# ElevenR3.net
KiCad netlist of a schematic drawn in EAGLE
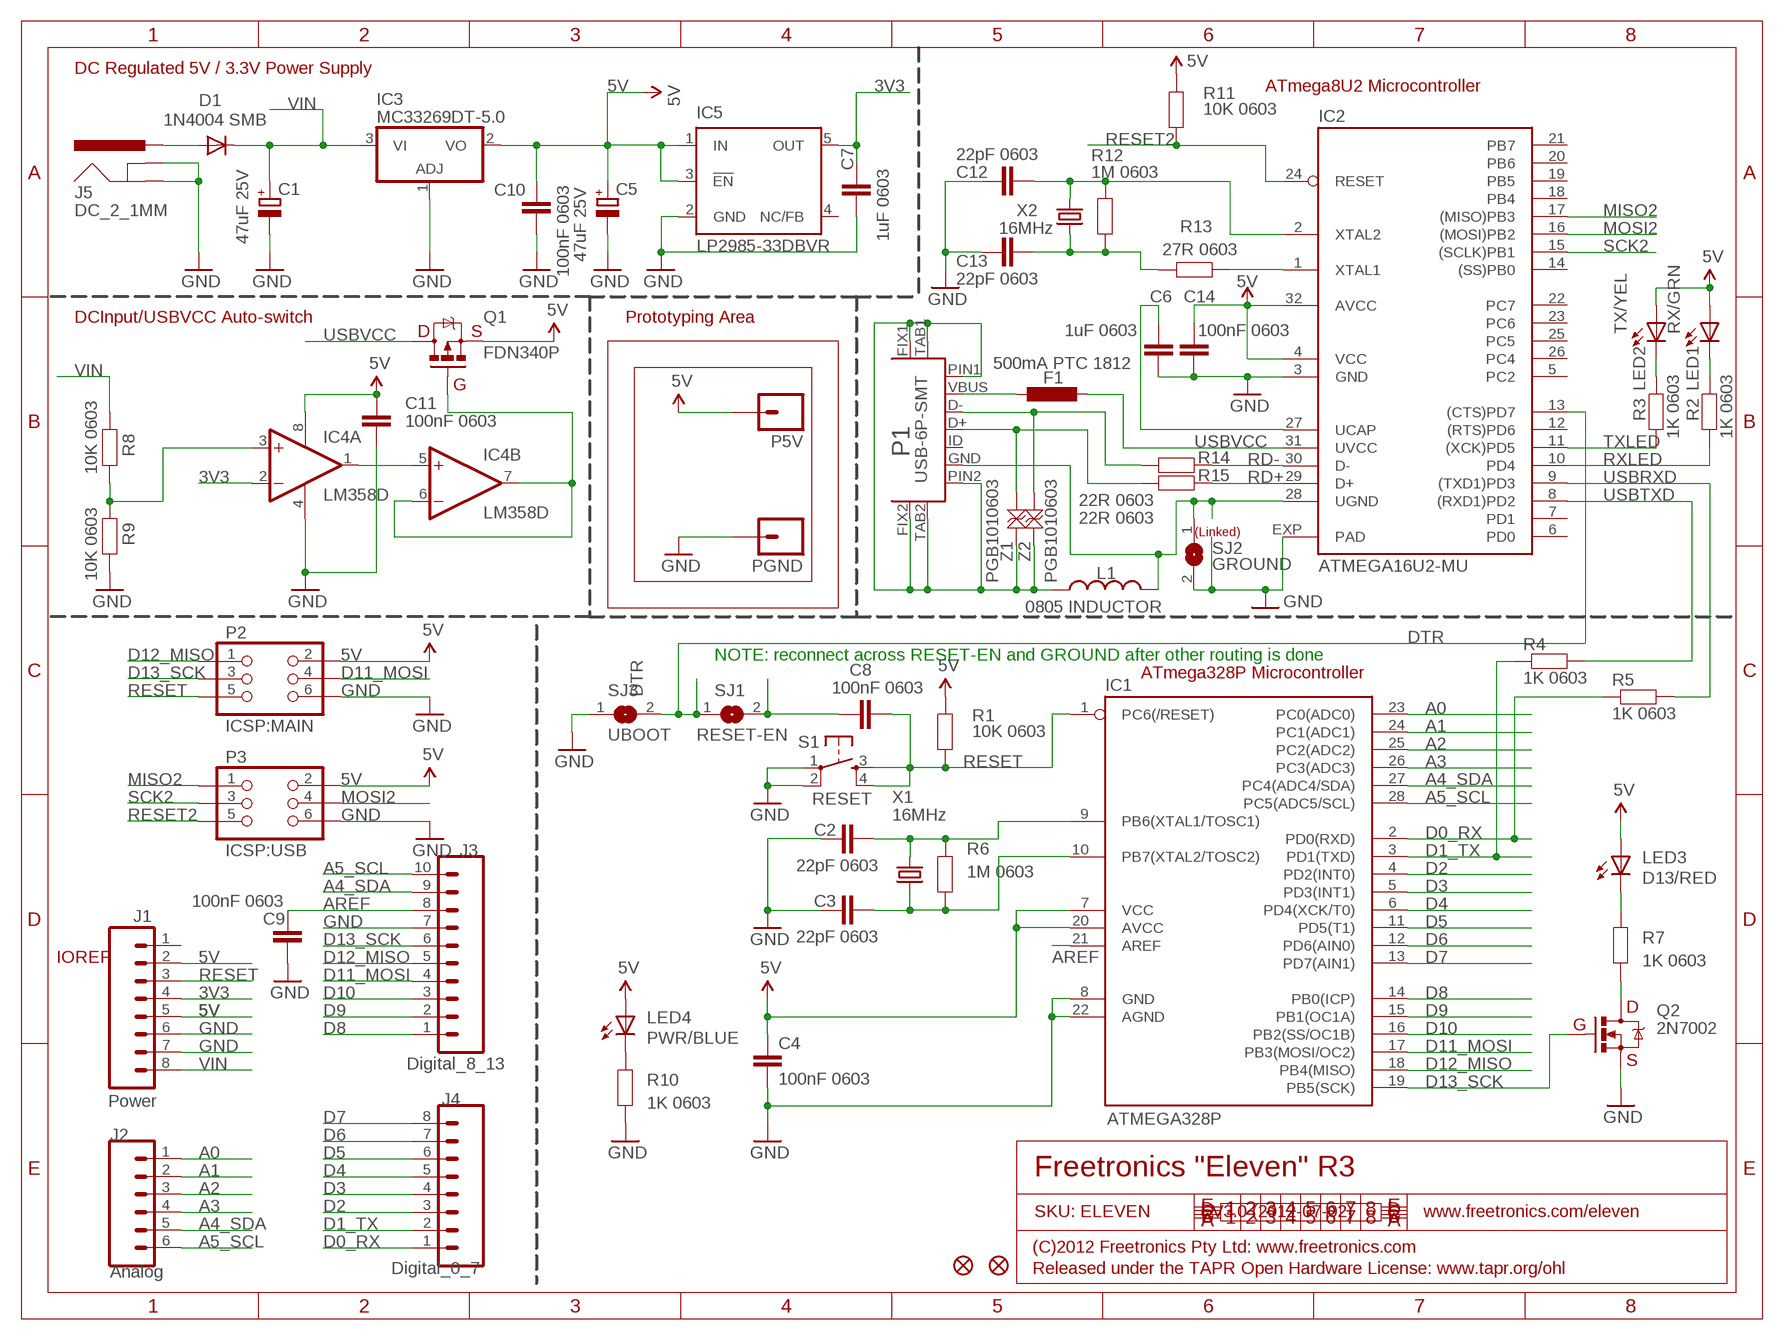
[diagram p0: schematic, sheet 1]

(export (version "E")
  (design (tool "Eeschema 10.0.6"))
  (components
    (comp (ref "C1")
      (value "47uF 25V")
      (footprint "eagle-import:PANASONIC_D")
      (libsource (lib "eagle-import") (part "CPOL-EUD"))
    )
    (comp (ref "C2")
      (value "22pF 0603")
      (footprint "eagle-import:C0603")
      (libsource (lib "eagle-import") (part "CAP0603"))
    )
    (comp (ref "C3")
      (value "22pF 0603")
      (footprint "eagle-import:C0603")
      (libsource (lib "eagle-import") (part "CAP0603"))
    )
    (comp (ref "C4")
      (value "100nF 0603")
      (footprint "eagle-import:C0603")
      (libsource (lib "eagle-import") (part "CAP0603"))
    )
    (comp (ref "C5")
      (value "47uF 25V")
      (footprint "eagle-import:PANASONIC_D")
      (libsource (lib "eagle-import") (part "CPOL-EUD"))
    )
    (comp (ref "C6")
      (value "1uF 0603")
      (footprint "eagle-import:C0603")
      (libsource (lib "eagle-import") (part "CAP0603"))
    )
    (comp (ref "C7")
      (value "1uF 0603")
      (footprint "eagle-import:C0603")
      (libsource (lib "eagle-import") (part "CAP0603"))
    )
    (comp (ref "C8")
      (value "100nF 0603")
      (footprint "eagle-import:C0603")
      (libsource (lib "eagle-import") (part "CAP0603"))
    )
    (comp (ref "C9")
      (value "100nF 0603")
      (footprint "eagle-import:C0603")
      (libsource (lib "eagle-import") (part "CAP0603"))
    )
    (comp (ref "C10")
      (value "100nF 0603")
      (footprint "eagle-import:C0603")
      (libsource (lib "eagle-import") (part "CAP0603"))
    )
    (comp (ref "C11")
      (value "100nF 0603")
      (footprint "eagle-import:C0603")
      (libsource (lib "eagle-import") (part "CAP0603"))
    )
    (comp (ref "C12")
      (value "22pF 0603")
      (footprint "eagle-import:C0603")
      (libsource (lib "eagle-import") (part "CAP0603"))
    )
    (comp (ref "C13")
      (value "22pF 0603")
      (footprint "eagle-import:C0603")
      (libsource (lib "eagle-import") (part "CAP0603"))
    )
    (comp (ref "C14")
      (value "100nF 0603")
      (footprint "eagle-import:C0603")
      (libsource (lib "eagle-import") (part "CAP0603"))
    )
    (comp (ref "D1")
      (value "1N4004 SMB")
      (footprint "eagle-import:SMA-DIODE")
      (libsource (lib "eagle-import") (part "DIODESMA"))
    )
    (comp (ref "F1")
      (value "500mA PTC 1812")
      (footprint "eagle-import:L1812")
      (libsource (lib "eagle-import") (part "L-EUL1812"))
    )
    (comp (ref "IC1")
      (value "ATMEGA328P")
      (footprint "eagle-import:DIL28-3")
      (libsource (lib "eagle-import") (part "AVR-MEGA8-P"))
    )
    (comp (ref "IC2")
      (value "ATMEGA16U2-MU")
      (footprint "eagle-import:ATMEL_QFN32")
      (libsource (lib "eagle-import") (part "ATMEGA8U2QFN"))
    )
    (comp (ref "IC3")
      (value "MC33269DT-5.0")
      (footprint "eagle-import:DPACK")
      (libsource (lib "eagle-import") (part "MC33269-X-D-5.0"))
    )
    (comp (ref "IC4")
      (value "LM358D")
      (footprint "eagle-import:SO08")
      (libsource (lib "eagle-import") (part "LM358D"))
    )
    (comp (ref "IC5")
      (value "LP2985-33DBVR")
      (footprint "eagle-import:TEXAS_SOT23-DBV")
      (libsource (lib "eagle-import") (part "LP2985-XX33"))
    )
    (comp (ref "J1")
      (value "Power")
      (footprint "eagle-import:1X08-S")
      (libsource (lib "eagle-import") (part "M08-SOCKET"))
    )
    (comp (ref "J2")
      (value "Analog")
      (footprint "eagle-import:1X06-S")
      (libsource (lib "eagle-import") (part "M06-SOCKET"))
    )
    (comp (ref "J3")
      (value "Digital_8_13")
      (footprint "eagle-import:1X10-S")
      (libsource (lib "eagle-import") (part "M10-SOCKET"))
    )
    (comp (ref "J4")
      (value "Digital_0_7")
      (footprint "eagle-import:1X08-S")
      (libsource (lib "eagle-import") (part "M08-SOCKET"))
    )
    (comp (ref "J5")
      (value "DC_2_1MM")
      (footprint "eagle-import:POWER_JACK_SLOTS")
      (libsource (lib "eagle-import") (part "POWER_JACK-SLOTS"))
    )
    (comp (ref "L1")
      (value "0805 INDUCTOR")
      (footprint "eagle-import:0805-LARGE")
      (libsource (lib "eagle-import") (part "INDUCTOR0805-LARGE"))
    )
    (comp (ref "LED1")
      (value "RX/GRN")
      (footprint "eagle-import:LED-0603")
      (libsource (lib "eagle-import") (part "LED0603"))
    )
    (comp (ref "LED2")
      (value "TX/YEL")
      (footprint "eagle-import:LED-0603")
      (libsource (lib "eagle-import") (part "LED0603"))
    )
    (comp (ref "LED3")
      (value "D13/RED")
      (footprint "eagle-import:LED-0603")
      (libsource (lib "eagle-import") (part "LED0603"))
    )
    (comp (ref "LED4")
      (value "PWR/BLUE")
      (footprint "eagle-import:LED-0603")
      (libsource (lib "eagle-import") (part "LED0603"))
    )
    (comp (ref "P1")
      (value "USB-6P-SMT")
      (footprint "eagle-import:USB-MICROB-MB05PMXX")
      (libsource (lib "eagle-import") (part "USB-6P-SMT"))
    )
    (comp (ref "P2")
      (value "ICSP:MAIN")
      (footprint "eagle-import:2X03PTH")
      (libsource (lib "eagle-import") (part "ICSPPTH"))
    )
    (comp (ref "P3")
      (value "ICSP:USB")
      (footprint "eagle-import:2X03PTH")
      (libsource (lib "eagle-import") (part "ICSPPTH"))
    )
    (comp (ref "P5V")
      (value "M01SMD")
      (footprint "eagle-import:LUXEON-PAD")
      (libsource (lib "eagle-import") (part "M01SMD"))
    )
    (comp (ref "PGND")
      (value "M01SMD")
      (footprint "eagle-import:LUXEON-PAD")
      (libsource (lib "eagle-import") (part "M01SMD"))
    )
    (comp (ref "Q1")
      (value "FDN340P")
      (footprint "eagle-import:SOT23-3")
      (libsource (lib "eagle-import") (part "MOSFET-PCHANNEL-SMT"))
    )
    (comp (ref "Q2")
      (value "2N7002")
      (footprint "eagle-import:SOT23-3")
      (libsource (lib "eagle-import") (part "MOSFET-NCHANNELSMD"))
    )
    (comp (ref "R1")
      (value "10K 0603")
      (footprint "eagle-import:R0603")
      (libsource (lib "eagle-import") (part "RESISTOR0603"))
    )
    (comp (ref "R2")
      (value "1K 0603")
      (footprint "eagle-import:R0603")
      (libsource (lib "eagle-import") (part "RESISTOR0603"))
    )
    (comp (ref "R3")
      (value "1K 0603")
      (footprint "eagle-import:R0603")
      (libsource (lib "eagle-import") (part "RESISTOR0603"))
    )
    (comp (ref "R4")
      (value "1K 0603")
      (footprint "eagle-import:R0603")
      (libsource (lib "eagle-import") (part "RESISTOR0603"))
    )
    (comp (ref "R5")
      (value "1K 0603")
      (footprint "eagle-import:R0603")
      (libsource (lib "eagle-import") (part "RESISTOR0603"))
    )
    (comp (ref "R6")
      (value "1M 0603")
      (footprint "eagle-import:R0603")
      (libsource (lib "eagle-import") (part "RESISTOR0603"))
    )
    (comp (ref "R7")
      (value "1K 0603")
      (footprint "eagle-import:R0603")
      (libsource (lib "eagle-import") (part "RESISTOR0603"))
    )
    (comp (ref "R8")
      (value "10K 0603")
      (footprint "eagle-import:R0603")
      (libsource (lib "eagle-import") (part "RESISTOR0603"))
    )
    (comp (ref "R9")
      (value "10K 0603")
      (footprint "eagle-import:R0603")
      (libsource (lib "eagle-import") (part "RESISTOR0603"))
    )
    (comp (ref "R10")
      (value "1K 0603")
      (footprint "eagle-import:R0603")
      (libsource (lib "eagle-import") (part "RESISTOR0603"))
    )
    (comp (ref "R11")
      (value "10K 0603")
      (footprint "eagle-import:R0603")
      (libsource (lib "eagle-import") (part "RESISTOR0603"))
    )
    (comp (ref "R12")
      (value "1M 0603")
      (footprint "eagle-import:R0603")
      (libsource (lib "eagle-import") (part "RESISTOR0603"))
    )
    (comp (ref "R13")
      (value "27R 0603")
      (footprint "eagle-import:R0603")
      (libsource (lib "eagle-import") (part "RESISTOR0603"))
    )
    (comp (ref "R14")
      (value "22R 0603")
      (footprint "eagle-import:R0603")
      (libsource (lib "eagle-import") (part "RESISTOR0603"))
    )
    (comp (ref "R15")
      (value "22R 0603")
      (footprint "eagle-import:R0603")
      (libsource (lib "eagle-import") (part "RESISTOR0603"))
    )
    (comp (ref "S1")
      (value "RESET")
      (footprint "eagle-import:TACTILE_SMD-6MM")
      (libsource (lib "eagle-import") (part "TAC_SWITCH-SMT-6"))
    )
    (comp (ref "SJ1")
      (value "RESET-EN")
      (footprint "eagle-import:SJ")
      (libsource (lib "eagle-import") (part "SJ"))
    )
    (comp (ref "SJ2")
      (value "GROUND")
      (footprint "eagle-import:SJ")
      (libsource (lib "eagle-import") (part "SJ"))
    )
    (comp (ref "SJ3")
      (value "UBOOT")
      (footprint "eagle-import:SJ")
      (libsource (lib "eagle-import") (part "SJ"))
    )
    (comp (ref "U$5")
      (value "FIDUCIAL1X2.5")
      (footprint "eagle-import:FIDUCIAL-1X2.5")
      (libsource (lib "eagle-import") (part "FIDUCIAL1X2.5"))
    )
    (comp (ref "U$14")
      (value "FIDUCIAL1X2.5")
      (footprint "eagle-import:FIDUCIAL-1X2.5")
      (libsource (lib "eagle-import") (part "FIDUCIAL1X2.5"))
    )
    (comp (ref "X1")
      (value "16MHz")
      (footprint "eagle-import:HC49U-V")
      (libsource (lib "eagle-import") (part "CRYSTALHC49UV"))
    )
    (comp (ref "X2")
      (value "16MHz")
      (footprint "eagle-import:HC49U-V")
      (libsource (lib "eagle-import") (part "CRYSTALHC49UV"))
    )
    (comp (ref "Z1")
      (value "PGB1010603")
      (footprint "eagle-import:TVS0603")
      (libsource (lib "eagle-import") (part "TVS0603"))
    )
    (comp (ref "Z2")
      (value "PGB1010603")
      (footprint "eagle-import:TVS0603")
      (libsource (lib "eagle-import") (part "TVS0603"))
    )
  )
  (nets
    (net (code "1") (name "/3V3") (class "Default")
      (node (ref "C7") (pin "2") (pinfunction "2_2") (pintype "passive"))
      (node (ref "IC4") (pin "2") (pinfunction "-IN_2") (pintype "input"))
      (node (ref "IC5") (pin "5") (pinfunction "OUT_5") (pintype "passive"))
      (node (ref "J1") (pin "4") (pinfunction "4_4") (pintype "passive"))
    )
    (net (code "2") (name "/A0") (class "Default")
      (node (ref "IC1") (pin "23") (pinfunction "PC0(ADC0)_23") (pintype "bidirectional"))
      (node (ref "J2") (pin "1") (pinfunction "1_1") (pintype "passive"))
    )
    (net (code "3") (name "/A1") (class "Default")
      (node (ref "IC1") (pin "24") (pinfunction "PC1(ADC1)_24") (pintype "bidirectional"))
      (node (ref "J2") (pin "2") (pinfunction "2_2") (pintype "passive"))
    )
    (net (code "4") (name "/A2") (class "Default")
      (node (ref "IC1") (pin "25") (pinfunction "PC2(ADC2)_25") (pintype "bidirectional"))
      (node (ref "J2") (pin "3") (pinfunction "3_3") (pintype "passive"))
    )
    (net (code "5") (name "/A3") (class "Default")
      (node (ref "IC1") (pin "26") (pinfunction "PC3(ADC3)_26") (pintype "bidirectional"))
      (node (ref "J2") (pin "4") (pinfunction "4_4") (pintype "passive"))
    )
    (net (code "6") (name "/A4_SDA") (class "Default")
      (node (ref "IC1") (pin "27") (pinfunction "PC4(ADC4/SDA)_27") (pintype "bidirectional"))
      (node (ref "J2") (pin "5") (pinfunction "5_5") (pintype "passive"))
      (node (ref "J3") (pin "9") (pinfunction "9_9") (pintype "passive"))
    )
    (net (code "7") (name "/A5_SCL") (class "Default")
      (node (ref "IC1") (pin "28") (pinfunction "PC5(ADC5/SCL)_28") (pintype "bidirectional"))
      (node (ref "J2") (pin "6") (pinfunction "6_6") (pintype "passive"))
      (node (ref "J3") (pin "10") (pinfunction "10_10") (pintype "passive"))
    )
    (net (code "8") (name "/AREF") (class "Default")
      (node (ref "C9") (pin "1") (pinfunction "1_1") (pintype "passive"))
      (node (ref "IC1") (pin "21") (pinfunction "AREF_21") (pintype "bidirectional"))
      (node (ref "J3") (pin "8") (pinfunction "8_8") (pintype "passive"))
    )
    (net (code "9") (name "/D0_RX") (class "Default")
      (node (ref "IC1") (pin "2") (pinfunction "PD0(RXD)_2") (pintype "bidirectional"))
      (node (ref "J4") (pin "1") (pinfunction "1_1") (pintype "passive"))
      (node (ref "R5") (pin "1") (pinfunction "1_1") (pintype "passive"))
    )
    (net (code "10") (name "/D1_TX") (class "Default")
      (node (ref "IC1") (pin "3") (pinfunction "PD1(TXD)_3") (pintype "bidirectional"))
      (node (ref "J4") (pin "2") (pinfunction "2_2") (pintype "passive"))
      (node (ref "R4") (pin "1") (pinfunction "1_1") (pintype "passive"))
    )
    (net (code "11") (name "/D2") (class "Default")
      (node (ref "IC1") (pin "4") (pinfunction "PD2(INT0)_4") (pintype "bidirectional"))
      (node (ref "J4") (pin "3") (pinfunction "3_3") (pintype "passive"))
    )
    (net (code "12") (name "/D3") (class "Default")
      (node (ref "IC1") (pin "5") (pinfunction "PD3(INT1)_5") (pintype "bidirectional"))
      (node (ref "J4") (pin "4") (pinfunction "4_4") (pintype "passive"))
    )
    (net (code "13") (name "/D4") (class "Default")
      (node (ref "IC1") (pin "6") (pinfunction "PD4(XCK/T0)_6") (pintype "bidirectional"))
      (node (ref "J4") (pin "5") (pinfunction "5_5") (pintype "passive"))
    )
    (net (code "14") (name "/D5") (class "Default")
      (node (ref "IC1") (pin "11") (pinfunction "PD5(T1)_11") (pintype "bidirectional"))
      (node (ref "J4") (pin "6") (pinfunction "6_6") (pintype "passive"))
    )
    (net (code "15") (name "/D6") (class "Default")
      (node (ref "IC1") (pin "12") (pinfunction "PD6(AIN0)_12") (pintype "bidirectional"))
      (node (ref "J4") (pin "7") (pinfunction "7_7") (pintype "passive"))
    )
    (net (code "16") (name "/D7") (class "Default")
      (node (ref "IC1") (pin "13") (pinfunction "PD7(AIN1)_13") (pintype "bidirectional"))
      (node (ref "J4") (pin "8") (pinfunction "8_8") (pintype "passive"))
    )
    (net (code "17") (name "/D8") (class "Default")
      (node (ref "IC1") (pin "14") (pinfunction "PB0(ICP)_14") (pintype "bidirectional"))
      (node (ref "J3") (pin "1") (pinfunction "1_1") (pintype "passive"))
    )
    (net (code "18") (name "/D9") (class "Default")
      (node (ref "IC1") (pin "15") (pinfunction "PB1(OC1A)_15") (pintype "bidirectional"))
      (node (ref "J3") (pin "2") (pinfunction "2_2") (pintype "passive"))
    )
    (net (code "19") (name "/D10") (class "Default")
      (node (ref "IC1") (pin "16") (pinfunction "PB2(SS/OC1B)_16") (pintype "bidirectional"))
      (node (ref "J3") (pin "3") (pinfunction "3_3") (pintype "passive"))
    )
    (net (code "20") (name "/D11_MOSI") (class "Default")
      (node (ref "IC1") (pin "17") (pinfunction "PB3(MOSI/OC2)_17") (pintype "bidirectional"))
      (node (ref "J3") (pin "4") (pinfunction "4_4") (pintype "passive"))
      (node (ref "P2") (pin "4") (pinfunction "4_4") (pintype "passive"))
    )
    (net (code "21") (name "/D12_MISO") (class "Default")
      (node (ref "IC1") (pin "18") (pinfunction "PB4(MISO)_18") (pintype "bidirectional"))
      (node (ref "J3") (pin "5") (pinfunction "5_5") (pintype "passive"))
      (node (ref "P2") (pin "1") (pinfunction "1_1") (pintype "passive"))
    )
    (net (code "22") (name "/D13_SCK") (class "Default")
      (node (ref "IC1") (pin "19") (pinfunction "PB5(SCK)_19") (pintype "bidirectional"))
      (node (ref "J3") (pin "6") (pinfunction "6_6") (pintype "passive"))
      (node (ref "P2") (pin "3") (pinfunction "3_3") (pintype "passive"))
      (node (ref "Q2") (pin "1") (pinfunction "G_1") (pintype "passive"))
    )
    (net (code "23") (name "/DTR") (class "Default")
      (node (ref "IC2") (pin "13") (pinfunction "(CTS)PD7_13") (pintype "bidirectional"))
      (node (ref "SJ1") (pin "1") (pinfunction "1_1") (pintype "passive"))
      (node (ref "SJ3") (pin "2") (pinfunction "2_2") (pintype "passive"))
    )
    (net (code "24") (name "/MISO2") (class "Default")
      (node (ref "IC2") (pin "17") (pinfunction "(MISO)PB3_17") (pintype "bidirectional"))
      (node (ref "P3") (pin "1") (pinfunction "1_1") (pintype "passive"))
    )
    (net (code "25") (name "/MOSI2") (class "Default")
      (node (ref "IC2") (pin "16") (pinfunction "(MOSI)PB2_16") (pintype "bidirectional"))
      (node (ref "P3") (pin "4") (pinfunction "4_4") (pintype "passive"))
    )
    (net (code "26") (name "/RD+") (class "Default")
      (node (ref "IC2") (pin "29") (pinfunction "D+_29") (pintype "bidirectional"))
      (node (ref "R15") (pin "1") (pinfunction "1_1") (pintype "passive"))
    )
    (net (code "27") (name "/RD-") (class "Default")
      (node (ref "IC2") (pin "30") (pinfunction "D-_30") (pintype "bidirectional"))
      (node (ref "R14") (pin "1") (pinfunction "1_1") (pintype "passive"))
    )
    (net (code "28") (name "/RESET") (class "Default")
      (node (ref "C8") (pin "2") (pinfunction "2_2") (pintype "passive"))
      (node (ref "IC1") (pin "1") (pinfunction "PC6(/RESET)_1") (pintype "bidirectional"))
      (node (ref "J1") (pin "3") (pinfunction "3_3") (pintype "passive"))
      (node (ref "P2") (pin "5") (pinfunction "5_5") (pintype "passive"))
      (node (ref "R1") (pin "1") (pinfunction "1_1") (pintype "passive"))
      (node (ref "S1") (pin "3") (pinfunction "3_3") (pintype "passive"))
      (node (ref "S1") (pin "4") (pinfunction "4_4") (pintype "passive"))
    )
    (net (code "29") (name "/RESET2") (class "Default")
      (node (ref "IC2") (pin "24") (pinfunction "RESET_24") (pintype "input"))
      (node (ref "P3") (pin "5") (pinfunction "5_5") (pintype "passive"))
      (node (ref "R11") (pin "1") (pinfunction "1_1") (pintype "passive"))
    )
    (net (code "30") (name "/RXLED") (class "Default")
      (node (ref "IC2") (pin "10") (pinfunction "PD4_10") (pintype "bidirectional"))
      (node (ref "R2") (pin "1") (pinfunction "1_1") (pintype "passive"))
    )
    (net (code "31") (name "/SCK2") (class "Default")
      (node (ref "IC2") (pin "15") (pinfunction "(SCLK)PB1_15") (pintype "bidirectional"))
      (node (ref "P3") (pin "3") (pinfunction "3_3") (pintype "passive"))
    )
    (net (code "32") (name "/TXLED") (class "Default")
      (node (ref "IC2") (pin "11") (pinfunction "(XCK)PD5_11") (pintype "bidirectional"))
      (node (ref "R3") (pin "1") (pinfunction "1_1") (pintype "passive"))
    )
    (net (code "33") (name "/USBRXD") (class "Default")
      (node (ref "IC2") (pin "9") (pinfunction "(TXD1)PD3_9") (pintype "bidirectional"))
      (node (ref "R5") (pin "2") (pinfunction "2_2") (pintype "passive"))
    )
    (net (code "34") (name "/USBTXD") (class "Default")
      (node (ref "IC2") (pin "8") (pinfunction "(RXD1)PD2_8") (pintype "bidirectional"))
      (node (ref "R4") (pin "2") (pinfunction "2_2") (pintype "passive"))
    )
    (net (code "35") (name "/USBVCC") (class "Default")
      (node (ref "F1") (pin "2") (pinfunction "2_2") (pintype "passive"))
      (node (ref "IC2") (pin "31") (pinfunction "UVCC_31") (pintype "power_in"))
      (node (ref "Q1") (pin "3") (pinfunction "D_3") (pintype "passive"))
    )
    (net (code "36") (name "/VIN") (class "Default")
      (node (ref "C1") (pin "+") (pinfunction "+_+") (pintype "passive"))
      (node (ref "D1") (pin "C") (pinfunction "C_C") (pintype "passive"))
      (node (ref "IC3") (pin "3") (pinfunction "VI_3") (pintype "input"))
      (node (ref "J1") (pin "8") (pinfunction "8_8") (pintype "passive"))
      (node (ref "R8") (pin "2") (pinfunction "2_2") (pintype "passive"))
    )
    (net (code "37") (name "5V") (class "Default")
      (node (ref "C10") (pin "1") (pinfunction "1_1") (pintype "passive"))
      (node (ref "C11") (pin "1") (pinfunction "1_1") (pintype "passive"))
      (node (ref "C14") (pin "1") (pinfunction "1_1") (pintype "passive"))
      (node (ref "C4") (pin "1") (pinfunction "1_1") (pintype "passive"))
      (node (ref "C5") (pin "+") (pinfunction "+_+") (pintype "passive"))
      (node (ref "IC1") (pin "20") (pinfunction "AVCC_20") (pintype "bidirectional"))
      (node (ref "IC1") (pin "7") (pinfunction "VCC_7") (pintype "bidirectional"))
      (node (ref "IC2") (pin "32") (pinfunction "AVCC_32") (pintype "power_in"))
      (node (ref "IC2") (pin "4") (pinfunction "VCC_4") (pintype "power_in"))
      (node (ref "IC3") (pin "2") (pinfunction "VO_2") (pintype "passive"))
      (node (ref "IC4") (pin "8") (pinfunction "V+_8") (pintype "power_in"))
      (node (ref "IC5") (pin "1") (pinfunction "IN_1") (pintype "input"))
      (node (ref "IC5") (pin "3") (pinfunction "~{EN}_3") (pintype "input"))
      (node (ref "J1") (pin "2") (pinfunction "2_2") (pintype "passive"))
      (node (ref "J1") (pin "5") (pinfunction "5_5") (pintype "passive"))
      (node (ref "LED1") (pin "A") (pinfunction "A_A") (pintype "passive"))
      (node (ref "LED2") (pin "A") (pinfunction "A_A") (pintype "passive"))
      (node (ref "LED3") (pin "A") (pinfunction "A_A") (pintype "passive"))
      (node (ref "LED4") (pin "A") (pinfunction "A_A") (pintype "passive"))
      (node (ref "P2") (pin "2") (pinfunction "2_2") (pintype "passive"))
      (node (ref "P3") (pin "2") (pinfunction "2_2") (pintype "passive"))
      (node (ref "P5V") (pin "P$1") (pinfunction "1_P$1") (pintype "passive"))
      (node (ref "Q1") (pin "2") (pinfunction "S_2") (pintype "passive"))
      (node (ref "R1") (pin "2") (pinfunction "2_2") (pintype "passive"))
      (node (ref "R11") (pin "2") (pinfunction "2_2") (pintype "passive"))
    )
    (net (code "38") (name "GND") (class "Default")
      (node (ref "C1") (pin "-") (pinfunction "-_-") (pintype "passive"))
      (node (ref "C10") (pin "2") (pinfunction "2_2") (pintype "passive"))
      (node (ref "C11") (pin "2") (pinfunction "2_2") (pintype "passive"))
      (node (ref "C12") (pin "1") (pinfunction "1_1") (pintype "passive"))
      (node (ref "C13") (pin "1") (pinfunction "1_1") (pintype "passive"))
      (node (ref "C14") (pin "2") (pinfunction "2_2") (pintype "passive"))
      (node (ref "C2") (pin "1") (pinfunction "1_1") (pintype "passive"))
      (node (ref "C3") (pin "1") (pinfunction "1_1") (pintype "passive"))
      (node (ref "C4") (pin "2") (pinfunction "2_2") (pintype "passive"))
      (node (ref "C5") (pin "-") (pinfunction "-_-") (pintype "passive"))
      (node (ref "C6") (pin "2") (pinfunction "2_2") (pintype "passive"))
      (node (ref "C7") (pin "1") (pinfunction "1_1") (pintype "passive"))
      (node (ref "C9") (pin "2") (pinfunction "2_2") (pintype "passive"))
      (node (ref "IC1") (pin "22") (pinfunction "AGND_22") (pintype "bidirectional"))
      (node (ref "IC1") (pin "8") (pinfunction "GND_8") (pintype "bidirectional"))
      (node (ref "IC2") (pin "3") (pinfunction "GND_3") (pintype "power_in"))
      (node (ref "IC2") (pin "EXP") (pinfunction "PAD_EXP") (pintype "power_in"))
      (node (ref "IC3") (pin "1") (pinfunction "ADJ_1") (pintype "input"))
      (node (ref "IC4") (pin "4") (pinfunction "V-_4") (pintype "power_in"))
      (node (ref "IC5") (pin "2") (pinfunction "GND_2") (pintype "power_in"))
      (node (ref "J1") (pin "6") (pinfunction "6_6") (pintype "passive"))
      (node (ref "J1") (pin "7") (pinfunction "7_7") (pintype "passive"))
      (node (ref "J3") (pin "7") (pinfunction "7_7") (pintype "passive"))
      (node (ref "J5") (pin "GND") (pinfunction "GND_GND") (pintype "bidirectional"))
      (node (ref "J5") (pin "GNDBREAK") (pinfunction "GNDBREAK_GNDBREAK") (pintype "bidirectional"))
      (node (ref "P2") (pin "6") (pinfunction "6_6") (pintype "passive"))
      (node (ref "P3") (pin "6") (pinfunction "6_6") (pintype "passive"))
      (node (ref "PGND") (pin "P$1") (pinfunction "1_P$1") (pintype "passive"))
      (node (ref "Q2") (pin "2") (pinfunction "S_2") (pintype "passive"))
      (node (ref "R10") (pin "1") (pinfunction "1_1") (pintype "passive"))
      (node (ref "R9") (pin "1") (pinfunction "1_1") (pintype "passive"))
      (node (ref "S1") (pin "1") (pinfunction "1_1") (pintype "passive"))
      (node (ref "S1") (pin "2") (pinfunction "2_2") (pintype "passive"))
      (node (ref "SJ2") (pin "2") (pinfunction "2_2") (pintype "passive"))
      (node (ref "SJ3") (pin "1") (pinfunction "1_1") (pintype "passive"))
    )
    (net (code "39") (name "Net-(C8-Pad1)") (class "Default")
      (node (ref "C8") (pin "1") (pinfunction "1_1") (pintype "passive"))
      (node (ref "SJ1") (pin "2") (pinfunction "2_2") (pintype "passive"))
    )
    (net (code "40") (name "Net-(C13-Pad2)") (class "Default")
      (node (ref "C13") (pin "2") (pinfunction "2_2") (pintype "passive"))
      (node (ref "R12") (pin "1") (pinfunction "1_1") (pintype "passive"))
      (node (ref "R13") (pin "2") (pinfunction "2_2") (pintype "passive"))
      (node (ref "X2") (pin "1") (pinfunction "1_1") (pintype "passive"))
    )
    (net (code "41") (name "Net-(D1-PadA)") (class "Default")
      (node (ref "D1") (pin "A") (pinfunction "A_A") (pintype "passive"))
      (node (ref "J5") (pin "PWR") (pinfunction "PWR_PWR") (pintype "bidirectional"))
    )
    (net (code "42") (name "Net-(F1-Pad1)") (class "Default")
      (node (ref "F1") (pin "1") (pinfunction "1_1") (pintype "passive"))
      (node (ref "P1") (pin "VBUS") (pinfunction "VBUS_VBUS") (pintype "bidirectional"))
    )
    (net (code "43") (name "Net-(IC1-PB6(XTAL1{slash}TOSC1))") (class "Default")
      (node (ref "C2") (pin "2") (pinfunction "2_2") (pintype "passive"))
      (node (ref "IC1") (pin "9") (pinfunction "PB6(XTAL1/TOSC1)_9") (pintype "bidirectional"))
      (node (ref "R6") (pin "2") (pinfunction "2_2") (pintype "passive"))
      (node (ref "X1") (pin "2") (pinfunction "2_2") (pintype "passive"))
    )
    (net (code "44") (name "Net-(IC1-PB7(XTAL2{slash}TOSC2))") (class "Default")
      (node (ref "C3") (pin "2") (pinfunction "2_2") (pintype "passive"))
      (node (ref "IC1") (pin "10") (pinfunction "PB7(XTAL2/TOSC2)_10") (pintype "bidirectional"))
      (node (ref "R6") (pin "1") (pinfunction "1_1") (pintype "passive"))
      (node (ref "X1") (pin "1") (pinfunction "1_1") (pintype "passive"))
    )
    (net (code "45") (name "Net-(IC2-UCAP)") (class "Default")
      (node (ref "C6") (pin "1") (pinfunction "1_1") (pintype "passive"))
      (node (ref "IC2") (pin "27") (pinfunction "UCAP_27") (pintype "passive"))
    )
    (net (code "46") (name "Net-(IC2-UGND)") (class "Default")
      (node (ref "IC2") (pin "28") (pinfunction "UGND_28") (pintype "power_in"))
      (node (ref "L1") (pin "2") (pinfunction "2_2") (pintype "passive"))
      (node (ref "P1") (pin "GND") (pinfunction "GND_GND") (pintype "bidirectional"))
      (node (ref "SJ2") (pin "1") (pinfunction "1_1") (pintype "passive"))
    )
    (net (code "47") (name "Net-(IC2-XTAL1)") (class "Default")
      (node (ref "IC2") (pin "1") (pinfunction "XTAL1_1") (pintype "bidirectional"))
      (node (ref "R13") (pin "1") (pinfunction "1_1") (pintype "passive"))
    )
    (net (code "48") (name "Net-(IC2-XTAL2)") (class "Default")
      (node (ref "C12") (pin "2") (pinfunction "2_2") (pintype "passive"))
      (node (ref "IC2") (pin "2") (pinfunction "XTAL2_2") (pintype "bidirectional"))
      (node (ref "R12") (pin "2") (pinfunction "2_2") (pintype "passive"))
      (node (ref "X2") (pin "2") (pinfunction "2_2") (pintype "passive"))
    )
    (net (code "49") (name "Net-(IC4A-+IN)") (class "Default")
      (node (ref "IC4") (pin "3") (pinfunction "+IN_3") (pintype "input"))
      (node (ref "R8") (pin "1") (pinfunction "1_1") (pintype "passive"))
      (node (ref "R9") (pin "2") (pinfunction "2_2") (pintype "passive"))
    )
    (net (code "50") (name "Net-(IC4A-OUT)") (class "Default")
      (node (ref "IC4") (pin "1") (pinfunction "OUT_1") (pintype "output"))
      (node (ref "IC4") (pin "5") (pinfunction "+IN_5") (pintype "input"))
    )
    (net (code "51") (name "Net-(IC4B--IN)") (class "Default")
      (node (ref "IC4") (pin "6") (pinfunction "-IN_6") (pintype "input"))
      (node (ref "IC4") (pin "7") (pinfunction "OUT_7") (pintype "output"))
      (node (ref "Q1") (pin "1") (pinfunction "G_1") (pintype "passive"))
    )
    (net (code "52") (name "Net-(L1-Pad1)") (class "Default")
      (node (ref "L1") (pin "1") (pinfunction "1_1") (pintype "passive"))
      (node (ref "P1") (pin "FIX1") (pinfunction "FIX1_FIX1") (pintype "bidirectional"))
      (node (ref "P1") (pin "FIX2") (pinfunction "FIX2_FIX2") (pintype "bidirectional"))
      (node (ref "P1") (pin "PIN1") (pinfunction "PIN1_PIN1") (pintype "bidirectional"))
      (node (ref "P1") (pin "PIN2") (pinfunction "PIN2_PIN2") (pintype "bidirectional"))
      (node (ref "P1") (pin "TAB1") (pinfunction "TAB1_TAB1") (pintype "bidirectional"))
      (node (ref "P1") (pin "TAB2") (pinfunction "TAB2_TAB2") (pintype "bidirectional"))
      (node (ref "Z1") (pin "2") (pinfunction "2_2") (pintype "passive"))
      (node (ref "Z2") (pin "2") (pinfunction "2_2") (pintype "passive"))
    )
    (net (code "53") (name "Net-(LED1-PadC)") (class "Default")
      (node (ref "LED1") (pin "C") (pinfunction "C_C") (pintype "passive"))
      (node (ref "R2") (pin "2") (pinfunction "2_2") (pintype "passive"))
    )
    (net (code "54") (name "Net-(LED2-PadC)") (class "Default")
      (node (ref "LED2") (pin "C") (pinfunction "C_C") (pintype "passive"))
      (node (ref "R3") (pin "2") (pinfunction "2_2") (pintype "passive"))
    )
    (net (code "55") (name "Net-(LED3-PadC)") (class "Default")
      (node (ref "LED3") (pin "C") (pinfunction "C_C") (pintype "passive"))
      (node (ref "R7") (pin "2") (pinfunction "2_2") (pintype "passive"))
    )
    (net (code "56") (name "Net-(LED4-PadC)") (class "Default")
      (node (ref "LED4") (pin "C") (pinfunction "C_C") (pintype "passive"))
      (node (ref "R10") (pin "2") (pinfunction "2_2") (pintype "passive"))
    )
    (net (code "57") (name "Net-(P1-PadD+)") (class "Default")
      (node (ref "P1") (pin "D+") (pinfunction "D+_D+") (pintype "bidirectional"))
      (node (ref "R15") (pin "2") (pinfunction "2_2") (pintype "passive"))
      (node (ref "Z1") (pin "1") (pinfunction "1_1") (pintype "passive"))
    )
    (net (code "58") (name "Net-(P1-PadD-)") (class "Default")
      (node (ref "P1") (pin "D-") (pinfunction "D-_D-") (pintype "bidirectional"))
      (node (ref "R14") (pin "2") (pinfunction "2_2") (pintype "passive"))
      (node (ref "Z2") (pin "1") (pinfunction "1_1") (pintype "passive"))
    )
    (net (code "59") (name "Net-(Q2-D)") (class "Default")
      (node (ref "Q2") (pin "3") (pinfunction "D_3") (pintype "passive"))
      (node (ref "R7") (pin "1") (pinfunction "1_1") (pintype "passive"))
    )
    (net (code "60") (name "unconnected-(IC2-(RTS)PD6-Pad12)") (class "Default")
      (node (ref "IC2") (pin "12") (pinfunction "(RTS)PD6_12") (pintype "bidirectional"))
    )
    (net (code "61") (name "unconnected-(IC2-(SS)PB0-Pad14)") (class "Default")
      (node (ref "IC2") (pin "14") (pinfunction "(SS)PB0_14") (pintype "bidirectional"))
    )
    (net (code "62") (name "unconnected-(IC2-PB4-Pad18)") (class "Default")
      (node (ref "IC2") (pin "18") (pinfunction "PB4_18") (pintype "bidirectional"))
    )
    (net (code "63") (name "unconnected-(IC2-PB5-Pad19)") (class "Default")
      (node (ref "IC2") (pin "19") (pinfunction "PB5_19") (pintype "bidirectional"))
    )
    (net (code "64") (name "unconnected-(IC2-PB6-Pad20)") (class "Default")
      (node (ref "IC2") (pin "20") (pinfunction "PB6_20") (pintype "bidirectional"))
    )
    (net (code "65") (name "unconnected-(IC2-PB7-Pad21)") (class "Default")
      (node (ref "IC2") (pin "21") (pinfunction "PB7_21") (pintype "bidirectional"))
    )
    (net (code "66") (name "unconnected-(IC2-PC2-Pad5)") (class "Default")
      (node (ref "IC2") (pin "5") (pinfunction "PC2_5") (pintype "bidirectional"))
    )
    (net (code "67") (name "unconnected-(IC2-PC4-Pad26)") (class "Default")
      (node (ref "IC2") (pin "26") (pinfunction "PC4_26") (pintype "bidirectional"))
    )
    (net (code "68") (name "unconnected-(IC2-PC5-Pad25)") (class "Default")
      (node (ref "IC2") (pin "25") (pinfunction "PC5_25") (pintype "bidirectional"))
    )
    (net (code "69") (name "unconnected-(IC2-PC6-Pad23)") (class "Default")
      (node (ref "IC2") (pin "23") (pinfunction "PC6_23") (pintype "bidirectional"))
    )
    (net (code "70") (name "unconnected-(IC2-PC7-Pad22)") (class "Default")
      (node (ref "IC2") (pin "22") (pinfunction "PC7_22") (pintype "bidirectional"))
    )
    (net (code "71") (name "unconnected-(IC2-PD0-Pad6)") (class "Default")
      (node (ref "IC2") (pin "6") (pinfunction "PD0_6") (pintype "bidirectional"))
    )
    (net (code "72") (name "unconnected-(IC2-PD1-Pad7)") (class "Default")
      (node (ref "IC2") (pin "7") (pinfunction "PD1_7") (pintype "bidirectional"))
    )
    (net (code "73") (name "unconnected-(IC5-NC{slash}FB-Pad4)") (class "Default")
      (node (ref "IC5") (pin "4") (pinfunction "NC/FB_4") (pintype "passive"))
    )
    (net (code "74") (name "unconnected-(J1-Pad1)") (class "Default")
      (node (ref "J1") (pin "1") (pinfunction "1_1") (pintype "passive"))
    )
    (net (code "75") (name "unconnected-(P1-PadID)") (class "Default")
      (node (ref "P1") (pin "ID") (pinfunction "ID_ID") (pintype "bidirectional"))
    )
  )
)
